# PROC099A_DUT_Reference.net
KiCad netlist of a schematic drawn in Altium Designer
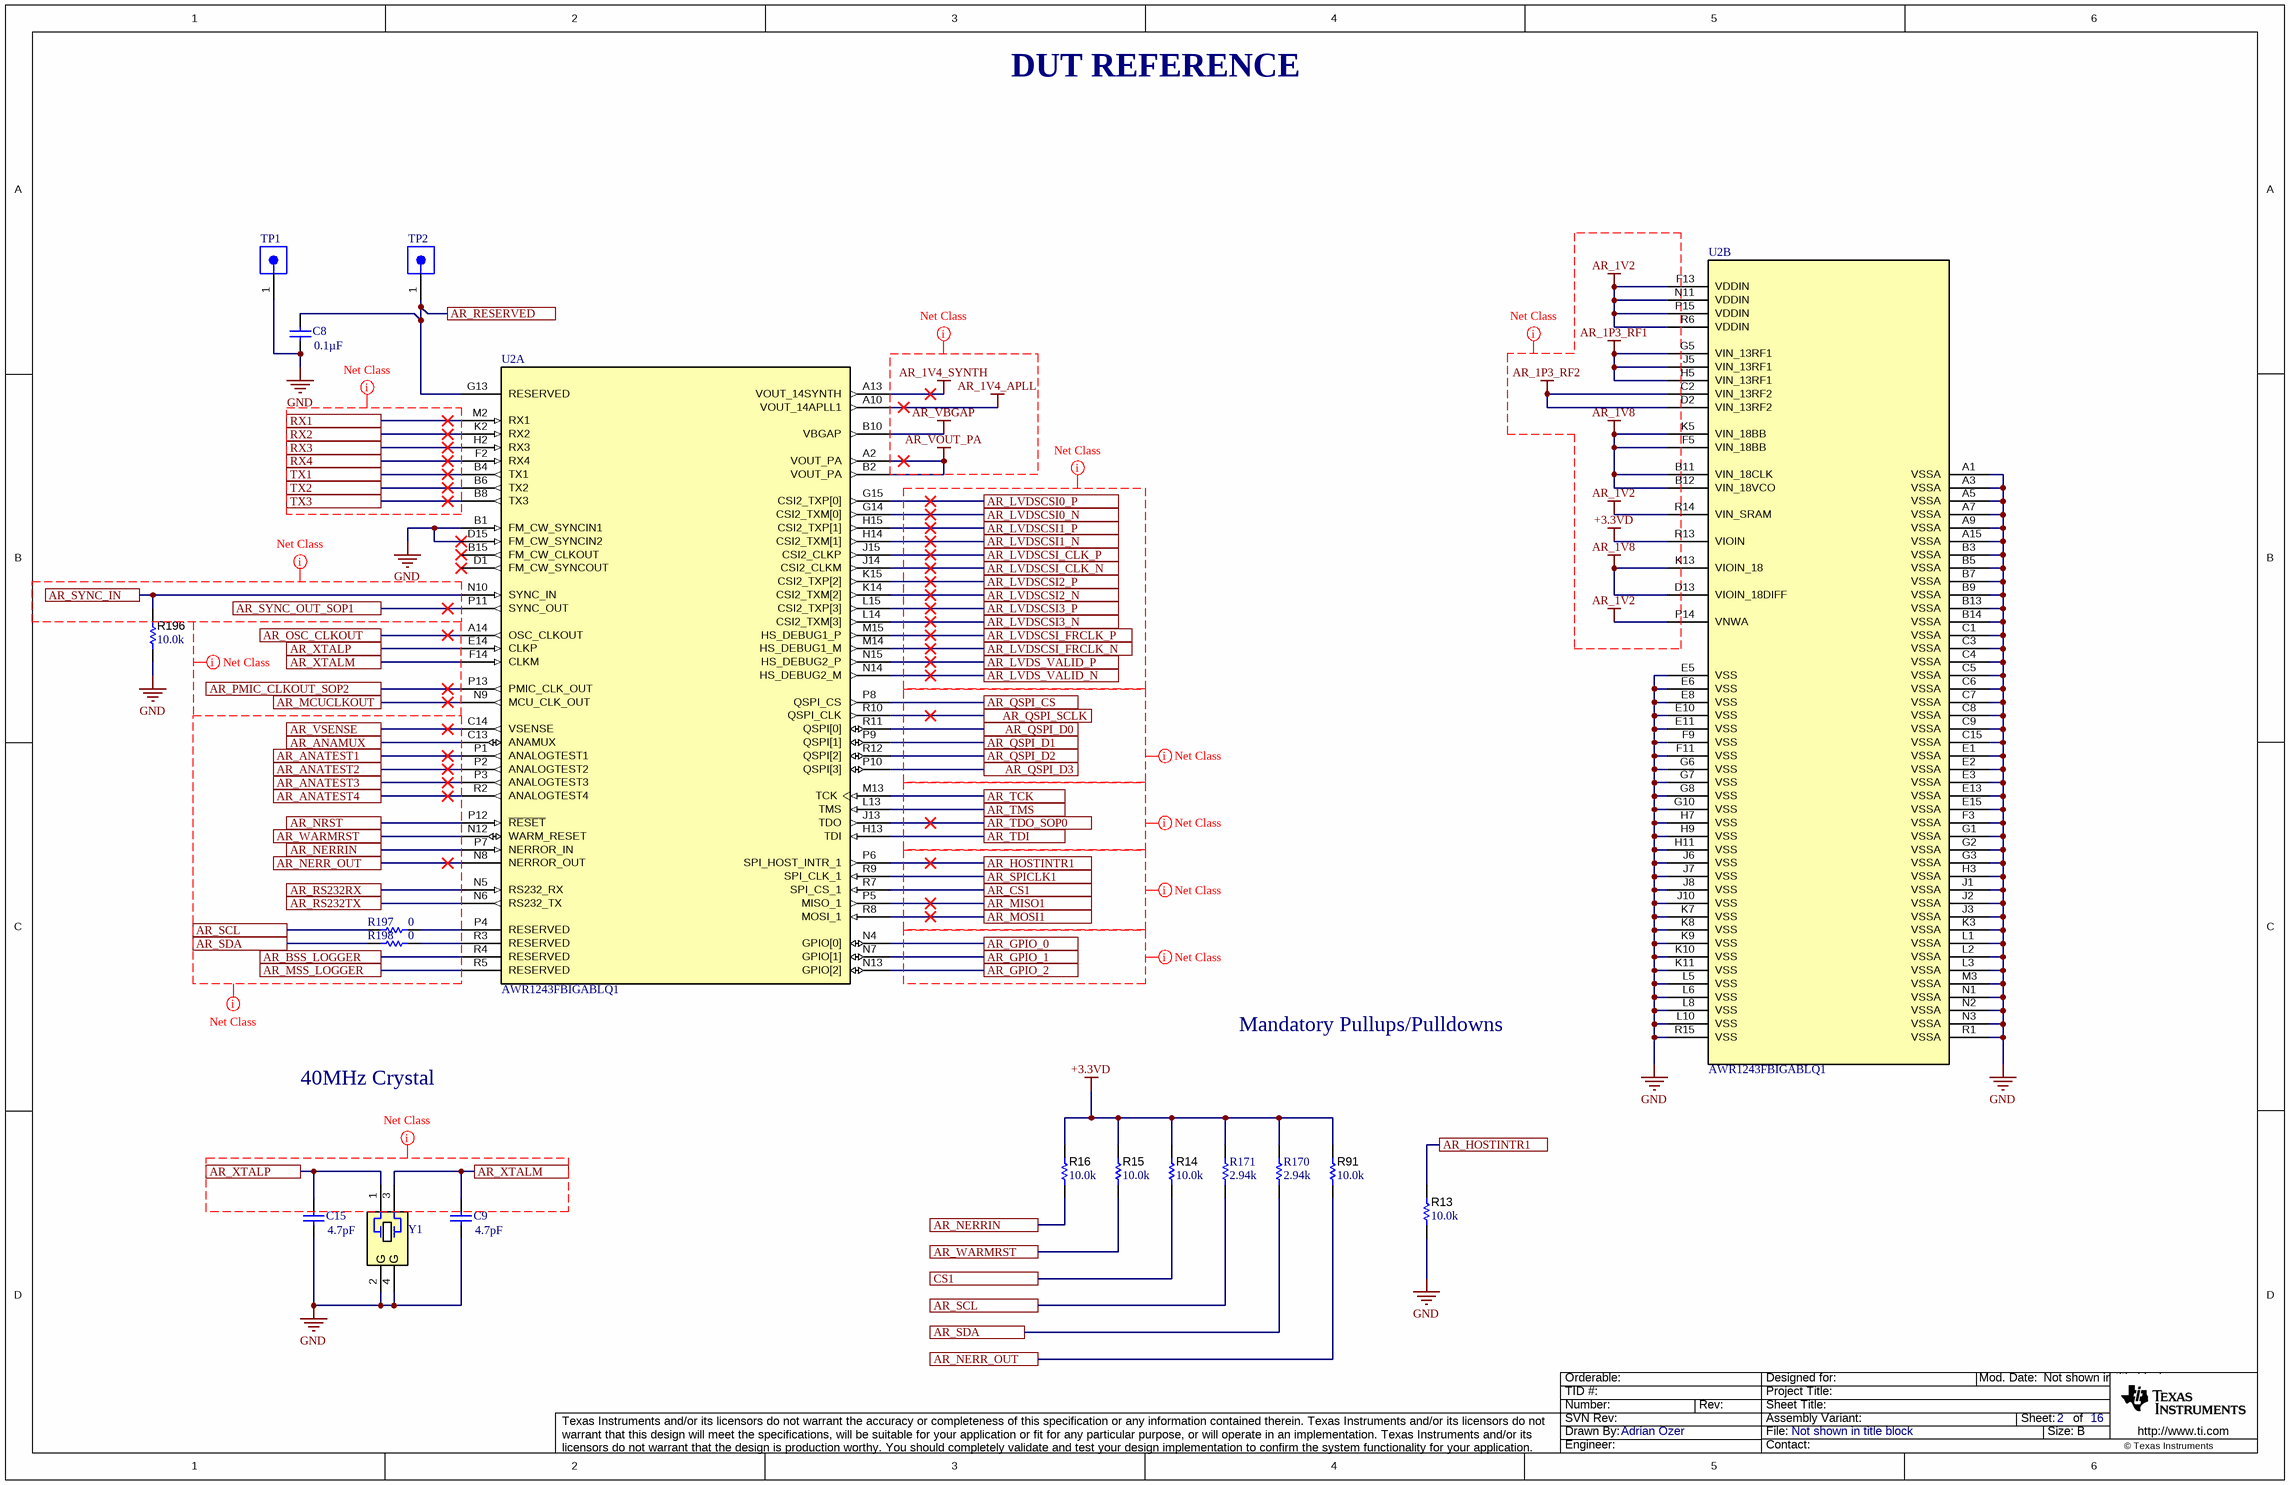
[diagram p0: PROC099A_DUT_Reference.SchDoc]

(export (version "E")
  (design (tool "Eeschema 10.0.6"))
  (components
    (comp (ref "C8")
      (value "C0603X7S1A104K030BC")
      (footprint "0201_033")
      (description "CAP, CERM, 0.1 µF, 10 V,+/- 10%, X7S, 0201")
      (fields (field (name "MANUFACTURER") "TDK") (field (name "VALUEDISPLAYED") "0.1µF"))
      (libsource (lib "Altium Vault - TI") (part "Capacitor"))
    )
    (comp (ref "C9")
      (value "GJM1555C1H4R7BB01D")
      (footprint "0402")
      (description "CAP, CERM, 4.7 pF, 50 V, +/- 2%, C0G/NP0, 0402")
      (fields
        (field (name "MANUFACTURER") "MuRata")
        (field (name "VALUEDISPLAYED") "4.7pF")
        (field (name "PUBLISHER") "Texas Instruments")
      )
      (libsource (lib "Altium Vault - TI") (part "CMP-0006367-2"))
    )
    (comp (ref "C15")
      (value "GJM1555C1H4R7BB01D")
      (footprint "0402")
      (description "CAP, CERM, 4.7 pF, 50 V, +/- 2%, C0G/NP0, 0402")
      (fields
        (field (name "MANUFACTURER") "MuRata")
        (field (name "VALUEDISPLAYED") "4.7pF")
        (field (name "PUBLISHER") "Texas Instruments")
      )
      (libsource (lib "Altium Vault - TI") (part "CMP-0006367-2"))
    )
    (comp (ref "R13")
      (value "CRCW040210K0FKED")
      (footprint "0402L")
      (description "RES, 10.0 k, 1%, 0.063 W, AEC-Q200 Grade 0, 0402")
      (fields (field (name "MANUFACTURER") "Vishay-Dale") (field (name "VALUEDISPLAYED") "10.0k"))
      (libsource (lib "Altium Vault - TI") (part "Resistor"))
    )
    (comp (ref "R14")
      (value "CRCW040210K0FKED")
      (footprint "0402L")
      (description "RES, 10.0 k, 1%, 0.063 W, AEC-Q200 Grade 0, 0402")
      (fields (field (name "MANUFACTURER") "Vishay-Dale") (field (name "VALUEDISPLAYED") "10.0k"))
      (libsource (lib "Altium Vault - TI") (part "Resistor"))
    )
    (comp (ref "R15")
      (value "CRCW040210K0FKED")
      (footprint "0402L")
      (description "RES, 10.0 k, 1%, 0.063 W, AEC-Q200 Grade 0, 0402")
      (fields (field (name "MANUFACTURER") "Vishay-Dale") (field (name "VALUEDISPLAYED") "10.0k"))
      (libsource (lib "Altium Vault - TI") (part "Resistor"))
    )
    (comp (ref "R16")
      (value "CRCW040210K0FKED")
      (footprint "0402L")
      (description "RES, 10.0 k, 1%, 0.063 W, AEC-Q200 Grade 0, 0402")
      (fields (field (name "MANUFACTURER") "Vishay-Dale") (field (name "VALUEDISPLAYED") "10.0k"))
      (libsource (lib "Altium Vault - TI") (part "Resistor"))
    )
    (comp (ref "R91")
      (value "CRCW040210K0FKED")
      (footprint "0402L")
      (description "RES, 10.0 k, 1%, 0.063 W, AEC-Q200 Grade 0, 0402")
      (fields (field (name "MANUFACTURER") "Vishay-Dale") (field (name "VALUEDISPLAYED") "10.0k"))
      (libsource (lib "Altium Vault - TI") (part "Resistor"))
    )
    (comp (ref "R170")
      (value "CRCW04022K94FKED")
      (footprint "0402")
      (description "RES, 2.94 k, 1%, 0.063 W, AEC-Q200 Grade 0, 0402")
      (fields (field (name "MANUFACTURER") "Vishay-Dale") (field (name "VALUEDISPLAYED") "2.94k"))
      (libsource (lib "Altium Vault - TI") (part "Resistor"))
    )
    (comp (ref "R171")
      (value "CRCW04022K94FKED")
      (footprint "0402")
      (description "RES, 2.94 k, 1%, 0.063 W, AEC-Q200 Grade 0, 0402")
      (fields (field (name "MANUFACTURER") "Vishay-Dale") (field (name "VALUEDISPLAYED") "2.94k"))
      (libsource (lib "Altium Vault - TI") (part "Resistor"))
    )
    (comp (ref "R196")
      (value "CRCW040210K0FKED")
      (footprint "0402L")
      (description "RES, 10.0 k, 1%, 0.063 W, AEC-Q200 Grade 0, 0402")
      (fields (field (name "MANUFACTURER") "Vishay-Dale") (field (name "VALUEDISPLAYED") "10.0k"))
      (libsource (lib "Altium Vault - TI") (part "CMP-0025958-3"))
    )
    (comp (ref "R197")
      (value "CRCW02010000Z0ED")
      (footprint "0201")
      (description "RES, 0, 5%, 0.05 W, 0201")
      (fields (field (name "MANUFACTURER") "Vishay-Dale") (field (name "VALUEDISPLAYED") "0"))
      (libsource (lib "Altium Vault - TI") (part "Resistor"))
    )
    (comp (ref "R198")
      (value "CRCW02010000Z0ED")
      (footprint "0201")
      (description "RES, 0, 5%, 0.05 W, 0201")
      (fields (field (name "MANUFACTURER") "Vishay-Dale") (field (name "VALUEDISPLAYED") "0"))
      (libsource (lib "Altium Vault - TI") (part "Resistor"))
    )
    (comp (ref "TP1")
      (value "TSW-101-17-T-S")
      (footprint "Samtec_TSW-101-17-T-S")
      (description "Header, 100mil, 1x1, Tin, TH")
      (fields (field (name "MANUFACTURER") "Samtec") (field (name "PUBLISHER") "Texas Instruments"))
      (libsource (lib "Altium Vault - TI") (part "Header_1x1"))
    )
    (comp (ref "TP2")
      (value "TSW-101-17-T-S")
      (footprint "Samtec_TSW-101-17-T-S")
      (description "Header, 100mil, 1x1, Tin, TH")
      (fields (field (name "MANUFACTURER") "Samtec") (field (name "PUBLISHER") "Texas Instruments"))
      (libsource (lib "Altium Vault - TI") (part "Header_1x1"))
    )
    (comp (ref "U2")
      (value "AWR1243FBIGABLQ1")
      (footprint "ABL0161A")
      (description "Single Chip 77 and 79 GHz FMCW Transceiver, ABL0161A (FCBGA-161)")
      (fields
        (field (name "ALTERNATE PARTNUMBER") "AWR1243FBIGABLRQ1")
        (field (name "MANUFACTURER") "Texas Instruments")
        (field (name "PARTNUMBER") "AWR1243FBIGABLQ1")
      )
      (libsource (lib "Altium Vault - TI") (part "CMP-0081285-1"))
    )
    (comp (ref "Y1")
      (value "CX3225SA40000D0PTWCC")
      (footprint "Kyocera_CX3225SA")
      (description "Crystal, 40 MHz, 8pF, SMD")
      (fields (field (name "MANUFACTURER") "Kyocera"))
      (libsource (lib "Altium Vault - TI") (part "XTAL_4P_13_24OPEN"))
    )
  )
  (nets
    (net (code "1") (name "+3.3VD") (class "Default")
      (node (ref "R14") (pin "2") (pinfunction "2_2") (pintype "passive"))
      (node (ref "R15") (pin "2") (pinfunction "2_2") (pintype "passive"))
      (node (ref "R16") (pin "2") (pinfunction "2_2") (pintype "passive"))
      (node (ref "R170") (pin "2") (pinfunction "2_2") (pintype "passive"))
      (node (ref "R171") (pin "2") (pinfunction "2_2") (pintype "passive"))
      (node (ref "R91") (pin "2") (pinfunction "2_2") (pintype "passive"))
      (node (ref "U2") (pin "R13") (pinfunction "VIOIN_R13") (pintype "power_in"))
    )
    (net (code "2") (name "/AR_ANAMUX") (class "Default")
      (node (ref "U2") (pin "C13") (pinfunction "ANAMUX_C13") (pintype "bidirectional"))
    )
    (net (code "3") (name "/AR_ANATEST1") (class "Default")
      (node (ref "U2") (pin "P1") (pinfunction "ANALOGTEST1_P1") (pintype "output"))
    )
    (net (code "4") (name "/AR_ANATEST2") (class "Default")
      (node (ref "U2") (pin "P2") (pinfunction "ANALOGTEST2_P2") (pintype "output"))
    )
    (net (code "5") (name "/AR_ANATEST3") (class "Default")
      (node (ref "U2") (pin "P3") (pinfunction "ANALOGTEST3_P3") (pintype "output"))
    )
    (net (code "6") (name "/AR_ANATEST4") (class "Default")
      (node (ref "U2") (pin "R2") (pinfunction "ANALOGTEST4_R2") (pintype "output"))
    )
    (net (code "7") (name "/AR_BSS_LOGGER") (class "Default")
      (node (ref "U2") (pin "R4") (pinfunction "RESERVED_R4") (pintype "passive"))
    )
    (net (code "8") (name "/AR_CS1") (class "Default")
      (node (ref "U2") (pin "R7") (pinfunction "SPI_CS_1_R7") (pintype "input"))
    )
    (net (code "9") (name "/AR_GPIO_0") (class "Default")
      (node (ref "U2") (pin "N4") (pinfunction "GPIO[0]_N4") (pintype "bidirectional"))
    )
    (net (code "10") (name "/AR_GPIO_1") (class "Default")
      (node (ref "U2") (pin "N7") (pinfunction "GPIO[1]_N7") (pintype "bidirectional"))
    )
    (net (code "11") (name "/AR_GPIO_2") (class "Default")
      (node (ref "U2") (pin "N13") (pinfunction "GPIO[2]_N13") (pintype "bidirectional"))
    )
    (net (code "12") (name "/AR_HOSTINTR1") (class "Default")
      (node (ref "R13") (pin "2") (pinfunction "2_2") (pintype "passive"))
      (node (ref "U2") (pin "P6") (pinfunction "SPI_HOST_INTR_1_P6") (pintype "output"))
    )
    (net (code "13") (name "/AR_LVDSCSI0_N") (class "Default")
      (node (ref "U2") (pin "G14") (pinfunction "CSI2_TXM[0]_G14") (pintype "output"))
    )
    (net (code "14") (name "/AR_LVDSCSI0_P") (class "Default")
      (node (ref "U2") (pin "G15") (pinfunction "CSI2_TXP[0]_G15") (pintype "output"))
    )
    (net (code "15") (name "/AR_LVDSCSI1_N") (class "Default")
      (node (ref "U2") (pin "H14") (pinfunction "CSI2_TXM[1]_H14") (pintype "output"))
    )
    (net (code "16") (name "/AR_LVDSCSI1_P") (class "Default")
      (node (ref "U2") (pin "H15") (pinfunction "CSI2_TXP[1]_H15") (pintype "output"))
    )
    (net (code "17") (name "/AR_LVDSCSI2_N") (class "Default")
      (node (ref "U2") (pin "K14") (pinfunction "CSI2_TXM[2]_K14") (pintype "output"))
    )
    (net (code "18") (name "/AR_LVDSCSI2_P") (class "Default")
      (node (ref "U2") (pin "K15") (pinfunction "CSI2_TXP[2]_K15") (pintype "output"))
    )
    (net (code "19") (name "/AR_LVDSCSI3_N") (class "Default")
      (node (ref "U2") (pin "L14") (pinfunction "CSI2_TXM[3]_L14") (pintype "output"))
    )
    (net (code "20") (name "/AR_LVDSCSI3_P") (class "Default")
      (node (ref "U2") (pin "L15") (pinfunction "CSI2_TXP[3]_L15") (pintype "output"))
    )
    (net (code "21") (name "/AR_LVDSCSI_CLK_N") (class "Default")
      (node (ref "U2") (pin "J14") (pinfunction "CSI2_CLKM_J14") (pintype "output"))
    )
    (net (code "22") (name "/AR_LVDSCSI_CLK_P") (class "Default")
      (node (ref "U2") (pin "J15") (pinfunction "CSI2_CLKP_J15") (pintype "output"))
    )
    (net (code "23") (name "/AR_LVDSCSI_FRCLK_N") (class "Default")
      (node (ref "U2") (pin "M14") (pinfunction "HS_DEBUG1_M_M14") (pintype "output"))
    )
    (net (code "24") (name "/AR_LVDSCSI_FRCLK_P") (class "Default")
      (node (ref "U2") (pin "M15") (pinfunction "HS_DEBUG1_P_M15") (pintype "output"))
    )
    (net (code "25") (name "/AR_LVDS_VALID_N") (class "Default")
      (node (ref "U2") (pin "N14") (pinfunction "HS_DEBUG2_M_N14") (pintype "output"))
    )
    (net (code "26") (name "/AR_LVDS_VALID_P") (class "Default")
      (node (ref "U2") (pin "N15") (pinfunction "HS_DEBUG2_P_N15") (pintype "output"))
    )
    (net (code "27") (name "/AR_MCUCLKOUT") (class "Default")
      (node (ref "U2") (pin "N9") (pinfunction "MCU_CLK_OUT_N9") (pintype "output"))
    )
    (net (code "28") (name "/AR_MISO1") (class "Default")
      (node (ref "U2") (pin "P5") (pinfunction "MISO_1_P5") (pintype "output"))
    )
    (net (code "29") (name "/AR_MOSI1") (class "Default")
      (node (ref "U2") (pin "R8") (pinfunction "MOSI_1_R8") (pintype "input"))
    )
    (net (code "30") (name "/AR_MSS_LOGGER") (class "Default")
      (node (ref "U2") (pin "R5") (pinfunction "RESERVED_R5") (pintype "passive"))
    )
    (net (code "31") (name "/AR_NERRIN") (class "Default")
      (node (ref "R16") (pin "1") (pinfunction "1_1") (pintype "passive"))
      (node (ref "U2") (pin "P7") (pinfunction "NERROR_IN_P7") (pintype "input"))
    )
    (net (code "32") (name "/AR_NERR_OUT") (class "Default")
      (node (ref "R91") (pin "1") (pinfunction "1_1") (pintype "passive"))
      (node (ref "U2") (pin "N8") (pinfunction "NERROR_OUT_N8") (pintype "open_collector"))
    )
    (net (code "33") (name "/AR_NRST") (class "Default")
      (node (ref "U2") (pin "P12") (pinfunction "RESET_P12") (pintype "input"))
    )
    (net (code "34") (name "/AR_OSC_CLKOUT") (class "Default")
      (node (ref "U2") (pin "A14") (pinfunction "OSC_CLKOUT_A14") (pintype "output"))
    )
    (net (code "35") (name "/AR_PMIC_CLKOUT_SOP2") (class "Default")
      (node (ref "U2") (pin "P13") (pinfunction "PMIC_CLK_OUT_P13") (pintype "output"))
    )
    (net (code "36") (name "/AR_QSPI_CS") (class "Default")
      (node (ref "U2") (pin "P8") (pinfunction "QSPI_CS_P8") (pintype "output"))
    )
    (net (code "37") (name "/AR_QSPI_D0") (class "Default")
      (node (ref "U2") (pin "R11") (pinfunction "QSPI[0]_R11") (pintype "bidirectional"))
    )
    (net (code "38") (name "/AR_QSPI_D1") (class "Default")
      (node (ref "U2") (pin "P9") (pinfunction "QSPI[1]_P9") (pintype "bidirectional"))
    )
    (net (code "39") (name "/AR_QSPI_D2") (class "Default")
      (node (ref "U2") (pin "R12") (pinfunction "QSPI[2]_R12") (pintype "bidirectional"))
    )
    (net (code "40") (name "/AR_QSPI_D3") (class "Default")
      (node (ref "U2") (pin "P10") (pinfunction "QSPI[3]_P10") (pintype "bidirectional"))
    )
    (net (code "41") (name "/AR_QSPI_SCLK") (class "Default")
      (node (ref "U2") (pin "R10") (pinfunction "QSPI_CLK_R10") (pintype "output"))
    )
    (net (code "42") (name "/AR_RESERVED") (class "Default")
      (node (ref "C8") (pin "1") (pinfunction "1_1") (pintype "passive"))
      (node (ref "TP2") (pin "1") (pinfunction "1_1") (pintype "passive"))
      (node (ref "U2") (pin "G13") (pinfunction "RESERVED_G13") (pintype "power_in"))
    )
    (net (code "43") (name "/AR_RS232RX") (class "Default")
      (node (ref "U2") (pin "N5") (pinfunction "RS232_RX_N5") (pintype "input"))
    )
    (net (code "44") (name "/AR_RS232TX") (class "Default")
      (node (ref "U2") (pin "N6") (pinfunction "RS232_TX_N6") (pintype "output"))
    )
    (net (code "45") (name "/AR_SCL") (class "Default")
      (node (ref "R171") (pin "1") (pinfunction "1_1") (pintype "passive"))
      (node (ref "R197") (pin "1") (pinfunction "1_1") (pintype "passive"))
    )
    (net (code "46") (name "/AR_SDA") (class "Default")
      (node (ref "R170") (pin "1") (pinfunction "1_1") (pintype "passive"))
      (node (ref "R198") (pin "1") (pinfunction "1_1") (pintype "passive"))
    )
    (net (code "47") (name "/AR_SPICLK1") (class "Default")
      (node (ref "U2") (pin "R9") (pinfunction "SPI_CLK_1_R9") (pintype "input"))
    )
    (net (code "48") (name "/AR_SYNC_IN") (class "Default")
      (node (ref "R196") (pin "2") (pinfunction "2_2") (pintype "passive"))
      (node (ref "U2") (pin "N10") (pinfunction "SYNC_IN_N10") (pintype "input"))
    )
    (net (code "49") (name "/AR_SYNC_OUT_SOP1") (class "Default")
      (node (ref "U2") (pin "P11") (pinfunction "SYNC_OUT_P11") (pintype "output"))
    )
    (net (code "50") (name "/AR_TCK") (class "Default")
      (node (ref "U2") (pin "M13") (pinfunction "TCK_M13") (pintype "input"))
    )
    (net (code "51") (name "/AR_TDI") (class "Default")
      (node (ref "U2") (pin "H13") (pinfunction "TDI_H13") (pintype "input"))
    )
    (net (code "52") (name "/AR_TDO_SOP0") (class "Default")
      (node (ref "U2") (pin "J13") (pinfunction "TDO_J13") (pintype "output"))
    )
    (net (code "53") (name "/AR_TMS") (class "Default")
      (node (ref "U2") (pin "L13") (pinfunction "TMS_L13") (pintype "input"))
    )
    (net (code "54") (name "/AR_VSENSE") (class "Default")
      (node (ref "U2") (pin "C14") (pinfunction "VSENSE_C14") (pintype "output"))
    )
    (net (code "55") (name "/AR_WARMRST") (class "Default")
      (node (ref "R15") (pin "1") (pinfunction "1_1") (pintype "passive"))
      (node (ref "U2") (pin "N12") (pinfunction "WARM_RESET_N12") (pintype "bidirectional"))
    )
    (net (code "56") (name "/AR_XTALM") (class "Default")
      (node (ref "C9") (pin "1") (pinfunction "1_1") (pintype "passive"))
      (node (ref "U2") (pin "F14") (pinfunction "CLKM_F14") (pintype "input"))
      (node (ref "Y1") (pin "3") (pinfunction "3_3") (pintype "passive"))
    )
    (net (code "57") (name "/AR_XTALP") (class "Default")
      (node (ref "C15") (pin "2") (pinfunction "2_2") (pintype "passive"))
      (node (ref "U2") (pin "E14") (pinfunction "CLKP_E14") (pintype "input"))
      (node (ref "Y1") (pin "1") (pinfunction "1_1") (pintype "passive"))
    )
    (net (code "58") (name "/CS1") (class "Default")
      (node (ref "R14") (pin "1") (pinfunction "1_1") (pintype "passive"))
    )
    (net (code "59") (name "/RX1") (class "Default")
      (node (ref "U2") (pin "M2") (pinfunction "RX1_M2") (pintype "input"))
    )
    (net (code "60") (name "/RX2") (class "Default")
      (node (ref "U2") (pin "K2") (pinfunction "RX2_K2") (pintype "input"))
    )
    (net (code "61") (name "/RX3") (class "Default")
      (node (ref "U2") (pin "H2") (pinfunction "RX3_H2") (pintype "input"))
    )
    (net (code "62") (name "/RX4") (class "Default")
      (node (ref "U2") (pin "F2") (pinfunction "RX4_F2") (pintype "input"))
    )
    (net (code "63") (name "/TX1") (class "Default")
      (node (ref "U2") (pin "B4") (pinfunction "TX1_B4") (pintype "output"))
    )
    (net (code "64") (name "/TX2") (class "Default")
      (node (ref "U2") (pin "B6") (pinfunction "TX2_B6") (pintype "output"))
    )
    (net (code "65") (name "/TX3") (class "Default")
      (node (ref "U2") (pin "B8") (pinfunction "TX3_B8") (pintype "output"))
    )
    (net (code "66") (name "AR_1P3_RF1") (class "Default")
      (node (ref "U2") (pin "G5") (pinfunction "VIN_13RF1_G5") (pintype "power_in"))
      (node (ref "U2") (pin "H5") (pinfunction "VIN_13RF1_H5") (pintype "power_in"))
      (node (ref "U2") (pin "J5") (pinfunction "VIN_13RF1_J5") (pintype "power_in"))
    )
    (net (code "67") (name "AR_1P3_RF2") (class "Default")
      (node (ref "U2") (pin "C2") (pinfunction "VIN_13RF2_C2") (pintype "power_in"))
      (node (ref "U2") (pin "D2") (pinfunction "VIN_13RF2_D2") (pintype "power_in"))
    )
    (net (code "68") (name "AR_1V2") (class "Default")
      (node (ref "U2") (pin "F13") (pinfunction "VDDIN_F13") (pintype "power_in"))
      (node (ref "U2") (pin "N11") (pinfunction "VDDIN_N11") (pintype "power_in"))
      (node (ref "U2") (pin "P14") (pinfunction "VNWA_P14") (pintype "power_in"))
      (node (ref "U2") (pin "P15") (pinfunction "VDDIN_P15") (pintype "power_in"))
      (node (ref "U2") (pin "R14") (pinfunction "VIN_SRAM_R14") (pintype "power_in"))
      (node (ref "U2") (pin "R6") (pinfunction "VDDIN_R6") (pintype "power_in"))
    )
    (net (code "69") (name "AR_1V4_APLL") (class "Default")
      (node (ref "U2") (pin "A10") (pinfunction "VOUT_14APLL1_A10") (pintype "output"))
    )
    (net (code "70") (name "AR_1V4_SYNTH") (class "Default")
      (node (ref "U2") (pin "A13") (pinfunction "VOUT_14SYNTH_A13") (pintype "output"))
    )
    (net (code "71") (name "AR_1V8") (class "Default")
      (node (ref "U2") (pin "B11") (pinfunction "VIN_18CLK_B11") (pintype "power_in"))
      (node (ref "U2") (pin "B12") (pinfunction "VIN_18VCO_B12") (pintype "power_in"))
      (node (ref "U2") (pin "D13") (pinfunction "VIOIN_18DIFF_D13") (pintype "power_in"))
      (node (ref "U2") (pin "F5") (pinfunction "VIN_18BB_F5") (pintype "power_in"))
      (node (ref "U2") (pin "K13") (pinfunction "VIOIN_18_K13") (pintype "power_in"))
      (node (ref "U2") (pin "K5") (pinfunction "VIN_18BB_K5") (pintype "power_in"))
    )
    (net (code "72") (name "AR_VBGAP") (class "Default")
      (node (ref "U2") (pin "B10") (pinfunction "VBGAP_B10") (pintype "output"))
    )
    (net (code "73") (name "AR_VOUT_PA") (class "Default")
      (node (ref "U2") (pin "A2") (pinfunction "VOUT_PA_A2") (pintype "output"))
      (node (ref "U2") (pin "B2") (pinfunction "VOUT_PA_B2") (pintype "output"))
    )
    (net (code "74") (name "GND") (class "Default")
      (node (ref "C15") (pin "1") (pinfunction "1_1") (pintype "passive"))
      (node (ref "C8") (pin "2") (pinfunction "2_2") (pintype "passive"))
      (node (ref "C9") (pin "2") (pinfunction "2_2") (pintype "passive"))
      (node (ref "R13") (pin "1") (pinfunction "1_1") (pintype "passive"))
      (node (ref "R196") (pin "1") (pinfunction "1_1") (pintype "passive"))
      (node (ref "TP1") (pin "1") (pinfunction "1_1") (pintype "passive"))
      (node (ref "U2") (pin "A1") (pinfunction "VSSA_A1") (pintype "power_in"))
      (node (ref "U2") (pin "A15") (pinfunction "VSSA_A15") (pintype "power_in"))
      (node (ref "U2") (pin "A3") (pinfunction "VSSA_A3") (pintype "power_in"))
      (node (ref "U2") (pin "A5") (pinfunction "VSSA_A5") (pintype "power_in"))
      (node (ref "U2") (pin "A7") (pinfunction "VSSA_A7") (pintype "power_in"))
      (node (ref "U2") (pin "A9") (pinfunction "VSSA_A9") (pintype "power_in"))
      (node (ref "U2") (pin "B1") (pinfunction "FM_CW_SYNCIN1_B1") (pintype "input"))
      (node (ref "U2") (pin "B13") (pinfunction "VSSA_B13") (pintype "power_in"))
      (node (ref "U2") (pin "B14") (pinfunction "VSSA_B14") (pintype "power_in"))
      (node (ref "U2") (pin "B3") (pinfunction "VSSA_B3") (pintype "power_in"))
      (node (ref "U2") (pin "B5") (pinfunction "VSSA_B5") (pintype "power_in"))
      (node (ref "U2") (pin "B7") (pinfunction "VSSA_B7") (pintype "power_in"))
      (node (ref "U2") (pin "B9") (pinfunction "VSSA_B9") (pintype "power_in"))
      (node (ref "U2") (pin "C1") (pinfunction "VSSA_C1") (pintype "power_in"))
      (node (ref "U2") (pin "C15") (pinfunction "VSSA_C15") (pintype "power_in"))
      (node (ref "U2") (pin "C3") (pinfunction "VSSA_C3") (pintype "power_in"))
      (node (ref "U2") (pin "C4") (pinfunction "VSSA_C4") (pintype "power_in"))
      (node (ref "U2") (pin "C5") (pinfunction "VSSA_C5") (pintype "power_in"))
      (node (ref "U2") (pin "C6") (pinfunction "VSSA_C6") (pintype "power_in"))
      (node (ref "U2") (pin "C7") (pinfunction "VSSA_C7") (pintype "power_in"))
      (node (ref "U2") (pin "C8") (pinfunction "VSSA_C8") (pintype "power_in"))
      (node (ref "U2") (pin "C9") (pinfunction "VSSA_C9") (pintype "power_in"))
      (node (ref "U2") (pin "D15") (pinfunction "FM_CW_SYNCIN2_D15") (pintype "input"))
      (node (ref "U2") (pin "E1") (pinfunction "VSSA_E1") (pintype "power_in"))
      (node (ref "U2") (pin "E10") (pinfunction "VSS_E10") (pintype "power_in"))
      (node (ref "U2") (pin "E11") (pinfunction "VSS_E11") (pintype "power_in"))
      (node (ref "U2") (pin "E13") (pinfunction "VSSA_E13") (pintype "power_in"))
      (node (ref "U2") (pin "E15") (pinfunction "VSSA_E15") (pintype "power_in"))
      (node (ref "U2") (pin "E2") (pinfunction "VSSA_E2") (pintype "power_in"))
      (node (ref "U2") (pin "E3") (pinfunction "VSSA_E3") (pintype "power_in"))
      (node (ref "U2") (pin "E5") (pinfunction "VSS_E5") (pintype "power_in"))
      (node (ref "U2") (pin "E6") (pinfunction "VSS_E6") (pintype "power_in"))
      (node (ref "U2") (pin "E8") (pinfunction "VSS_E8") (pintype "power_in"))
      (node (ref "U2") (pin "F11") (pinfunction "VSS_F11") (pintype "power_in"))
      (node (ref "U2") (pin "F3") (pinfunction "VSSA_F3") (pintype "power_in"))
      (node (ref "U2") (pin "F9") (pinfunction "VSS_F9") (pintype "power_in"))
      (node (ref "U2") (pin "G1") (pinfunction "VSSA_G1") (pintype "power_in"))
      (node (ref "U2") (pin "G10") (pinfunction "VSS_G10") (pintype "power_in"))
      (node (ref "U2") (pin "G2") (pinfunction "VSSA_G2") (pintype "power_in"))
      (node (ref "U2") (pin "G3") (pinfunction "VSSA_G3") (pintype "power_in"))
      (node (ref "U2") (pin "G6") (pinfunction "VSS_G6") (pintype "power_in"))
      (node (ref "U2") (pin "G7") (pinfunction "VSS_G7") (pintype "power_in"))
      (node (ref "U2") (pin "G8") (pinfunction "VSS_G8") (pintype "power_in"))
      (node (ref "U2") (pin "H11") (pinfunction "VSS_H11") (pintype "power_in"))
      (node (ref "U2") (pin "H3") (pinfunction "VSSA_H3") (pintype "power_in"))
      (node (ref "U2") (pin "H7") (pinfunction "VSS_H7") (pintype "power_in"))
      (node (ref "U2") (pin "H9") (pinfunction "VSS_H9") (pintype "power_in"))
      (node (ref "U2") (pin "J1") (pinfunction "VSSA_J1") (pintype "power_in"))
      (node (ref "U2") (pin "J10") (pinfunction "VSS_J10") (pintype "power_in"))
      (node (ref "U2") (pin "J2") (pinfunction "VSSA_J2") (pintype "power_in"))
      (node (ref "U2") (pin "J3") (pinfunction "VSSA_J3") (pintype "power_in"))
      (node (ref "U2") (pin "J6") (pinfunction "VSS_J6") (pintype "power_in"))
      (node (ref "U2") (pin "J7") (pinfunction "VSS_J7") (pintype "power_in"))
      (node (ref "U2") (pin "J8") (pinfunction "VSS_J8") (pintype "power_in"))
      (node (ref "U2") (pin "K10") (pinfunction "VSS_K10") (pintype "power_in"))
      (node (ref "U2") (pin "K11") (pinfunction "VSS_K11") (pintype "power_in"))
      (node (ref "U2") (pin "K3") (pinfunction "VSSA_K3") (pintype "power_in"))
      (node (ref "U2") (pin "K7") (pinfunction "VSS_K7") (pintype "power_in"))
      (node (ref "U2") (pin "K8") (pinfunction "VSS_K8") (pintype "power_in"))
      (node (ref "U2") (pin "K9") (pinfunction "VSS_K9") (pintype "power_in"))
      (node (ref "U2") (pin "L1") (pinfunction "VSSA_L1") (pintype "power_in"))
      (node (ref "U2") (pin "L10") (pinfunction "VSS_L10") (pintype "power_in"))
      (node (ref "U2") (pin "L2") (pinfunction "VSSA_L2") (pintype "power_in"))
      (node (ref "U2") (pin "L3") (pinfunction "VSSA_L3") (pintype "power_in"))
      (node (ref "U2") (pin "L5") (pinfunction "VSS_L5") (pintype "power_in"))
      (node (ref "U2") (pin "L6") (pinfunction "VSS_L6") (pintype "power_in"))
      (node (ref "U2") (pin "L8") (pinfunction "VSS_L8") (pintype "power_in"))
      (node (ref "U2") (pin "M3") (pinfunction "VSSA_M3") (pintype "power_in"))
      (node (ref "U2") (pin "N1") (pinfunction "VSSA_N1") (pintype "power_in"))
      (node (ref "U2") (pin "N2") (pinfunction "VSSA_N2") (pintype "power_in"))
      (node (ref "U2") (pin "N3") (pinfunction "VSSA_N3") (pintype "power_in"))
      (node (ref "U2") (pin "R1") (pinfunction "VSSA_R1") (pintype "power_in"))
      (node (ref "U2") (pin "R15") (pinfunction "VSS_R15") (pintype "power_in"))
      (node (ref "Y1") (pin "2") (pinfunction "GND_2") (pintype "power_in"))
      (node (ref "Y1") (pin "4") (pinfunction "GND_4") (pintype "power_in"))
    )
    (net (code "75") (name "Net-(R197-Pad2)") (class "Default")
      (node (ref "R197") (pin "2") (pinfunction "2_2") (pintype "passive"))
      (node (ref "U2") (pin "P4") (pinfunction "RESERVED_P4") (pintype "passive"))
    )
    (net (code "76") (name "Net-(R198-Pad2)") (class "Default")
      (node (ref "R198") (pin "2") (pinfunction "2_2") (pintype "passive"))
      (node (ref "U2") (pin "R3") (pinfunction "RESERVED_R3") (pintype "passive"))
    )
    (net (code "77") (name "unconnected-(U2A-FM_CW_CLKOUT-PadB15)") (class "Default")
      (node (ref "U2") (pin "B15") (pinfunction "FM_CW_CLKOUT_B15") (pintype "output+no_connect"))
    )
    (net (code "78") (name "unconnected-(U2A-FM_CW_SYNCOUT-PadD1)") (class "Default")
      (node (ref "U2") (pin "D1") (pinfunction "FM_CW_SYNCOUT_D1") (pintype "output+no_connect"))
    )
  )
)
